# Sheet1.net
KiCad netlist of a schematic drawn in Altium Designer
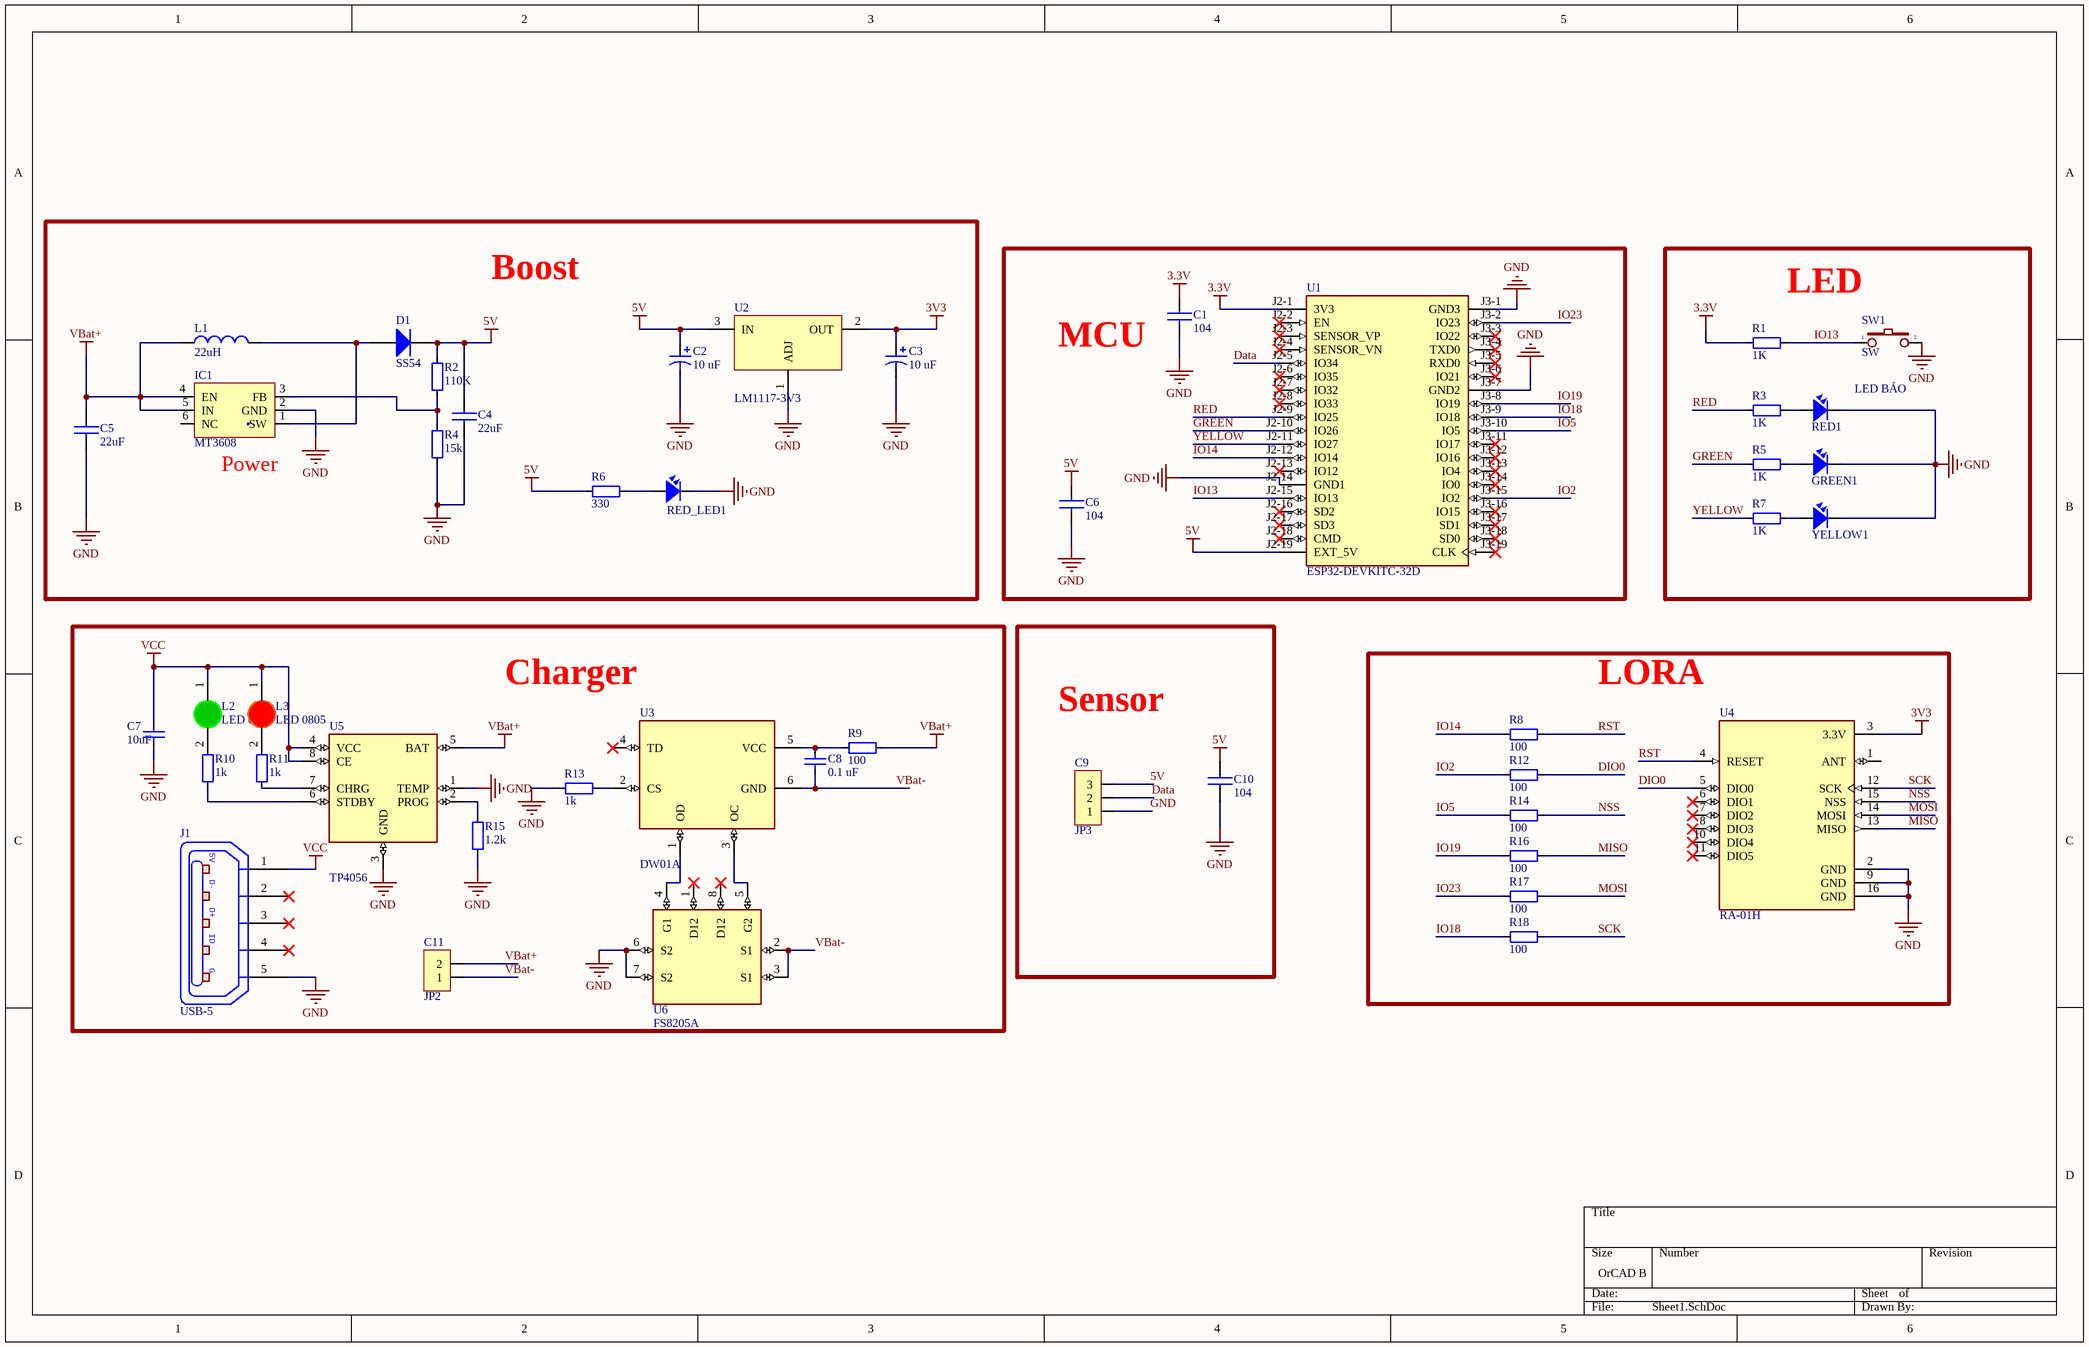
[diagram p0: Sheet1.SchDoc]

(export (version "E")
  (design (tool "Eeschema 10.0.6"))
  (components
    (comp (ref "C1")
      (value "104")
      (footprint "CAP0603")
      (description "CAP CER 30PF 50V NPO 0603")
      (fields
        (field (name "MANUFACTURER") "Yageo")
        (field (name "MANUFACTURER PART NUMBER") "CC0603JRNPO9BN300")
      )
      (libsource (lib "KhanhBK_SCH_Lib_6") (part "CC0603JRNPO9BN300"))
    )
    (comp (ref "C2")
      (value "10 uF")
      (footprint "C3MM")
      (description "Polarized Capacitor (Axial)")
      (fields (field (name "PUBLISHER") "Altium Limited"))
      (libsource (lib "My Library") (part "Cap Pol"))
    )
    (comp (ref "C3")
      (value "10 uF")
      (footprint "C3MM")
      (description "Polarized Capacitor (Axial)")
      (fields (field (name "PUBLISHER") "Altium Limited"))
      (libsource (lib "My Library") (part "Cap Pol"))
    )
    (comp (ref "C4")
      (value "22uF")
      (footprint "CAP0603")
      (description "CAP CER 30PF 50V NPO 0603")
      (fields
        (field (name "MANUFACTURER") "Yageo")
        (field (name "MANUFACTURER PART NUMBER") "CC0603JRNPO9BN300")
      )
      (libsource (lib "KhanhBK_SCH_Lib_6") (part "CC0603JRNPO9BN300"))
    )
    (comp (ref "C5")
      (value "22uF")
      (footprint "CAP0603")
      (description "CAP CER 30PF 50V NPO 0603")
      (fields
        (field (name "MANUFACTURER") "Yageo")
        (field (name "MANUFACTURER PART NUMBER") "CC0603JRNPO9BN300")
      )
      (libsource (lib "KhanhBK_SCH_Lib_6") (part "CC0603JRNPO9BN300"))
    )
    (comp (ref "C6")
      (value "104")
      (footprint "CAP0603")
      (description "CAP CER 30PF 50V NPO 0603")
      (fields
        (field (name "MANUFACTURER") "Yageo")
        (field (name "MANUFACTURER PART NUMBER") "CC0603JRNPO9BN300")
      )
      (libsource (lib "KhanhBK_SCH_Lib_6") (part "CC0603JRNPO9BN300"))
    )
    (comp (ref "C7")
      (value "10uF")
      (footprint "CAP_0805")
      (description "Capacitor")
      (fields (field (name "PUBLISHER") "Altium Limited"))
      (libsource (lib "My Library") (part "CapSMD"))
    )
    (comp (ref "C8")
      (value "0.1 uF")
      (footprint "CAP_0805")
      (description "Capacitor")
      (fields (field (name "PUBLISHER") "Altium Limited"))
      (libsource (lib "My Library") (part "CapSMD"))
    )
    (comp (ref "C9")
      (value "JP3")
      (footprint "JP3-C1T")
      (description "WR-PHD 2.54 mm Angled Socket Header")
      (fields
        (field (name "MANUFACTURER") "Würth Elektronik eiSos GmbH")
        (field (name "PARTNO") "613003143121")
        (field (name "CREATED BY") "Karrer Zheng")
      )
      (libsource (lib "KhanhBK_SCH_Library_1") (part "JP3"))
    )
    (comp (ref "C10")
      (value "104")
      (footprint "CAP0603")
      (description "CAP CER 30PF 50V NPO 0603")
      (fields
        (field (name "MANUFACTURER") "Yageo")
        (field (name "MANUFACTURER PART NUMBER") "CC0603JRNPO9BN300")
      )
      (libsource (lib "KhanhBK_SCH_Lib_6") (part "CC0603JRNPO9BN300"))
    )
    (comp (ref "C11")
      (value "JP2")
      (footprint "JP2-C1T")
      (description "WR-PHD 2.54 mm Angled Socket Header")
      (fields
        (field (name "MANUFACTURER") "Würth Elektronik eiSos GmbH")
        (field (name "PARTNO") "613002143121")
        (field (name "CREATED BY") "Karrer Zheng")
      )
      (libsource (lib "KhanhBK_SCH_Library_1") (part "JP2"))
    )
    (comp (ref "D1")
      (value "SS54")
      (footprint "DIODE/POW/1A")
      (description "Diode Power")
      (fields (field (name "PUBLISHER") "Altium Limited"))
      (libsource (lib "Cty1") (part "Diode Power"))
    )
    (comp (ref "GREEN1")
      (value "LED")
      (footprint "LED-3MM-GREEN")
      (description "LED Single colour Green and Red")
      (libsource (lib "KhanhBK_SCH_Library_1") (part "LED"))
    )
    (comp (ref "IC1") (value "MT3608") (footprint "TSOP 2") (libsource (lib "MT3608") (part "MT3608")))
    (comp (ref "J1")
      (value "USB-5")
      (footprint "USB-M1")
      (fields
        (field (name "MANUFACTURER") "FCI")
        (field (name "MANUFACTURER PART NUMBER") "10118193-0001LF")
        (field (name ".CREATOR") "MM")
        (field (name ".CHECKED PCB") "RF")
        (field (name ".CHECKED SCH") "MM")
      )
      (libsource (lib "My Library") (part "USB-5"))
    )
    (comp (ref "L1")
      (value "22uH")
      (footprint "IND_400_500_212x114_SMD")
      (description "1mH Shielded Wirewound Inductor 600mA 1.82Ohm Max Nonstandard")
      (fields (field (name "MANUFACTURER") "Coilcraft") (field (name "MANUFACTURER PART NUMBER") "74477030"))
      (libsource (lib "Altium_Lib_by_KhueNguyenCreator") (part "IND_1mH-0.6A-20%-SMD"))
    )
    (comp (ref "L2")
      (value "LED 0805")
      (footprint "LED-0805-Green")
      (description "Dán")
      (libsource (lib "Altium_Lib_by_KhueNguyenCreator") (part "LED 0805 Xanh La"))
    )
    (comp (ref "L3")
      (value "LED 0805")
      (footprint "LED-0805-Red")
      (description "Dán")
      (libsource (lib "Altium_Lib_by_KhueNguyenCreator") (part "LED 0805 Do"))
    )
    (comp (ref "R1")
      (value "1K")
      (footprint "RES-SMD-0805")
      (description "Resistor")
      (fields
        (field (name "MANUFACTURER") "Generic Components")
        (field (name "PUBLISHER") "Altium Hobart Technology Centre")
      )
      (libsource (lib "My Library") (part "Resistor - SMD"))
    )
    (comp (ref "R2")
      (value "110K")
      (footprint "RES-SMD-0805")
      (description "Resistor")
      (fields
        (field (name "MANUFACTURER") "Generic Components")
        (field (name "PUBLISHER") "Altium Hobart Technology Centre")
      )
      (libsource (lib "My Library") (part "Resistor - SMD"))
    )
    (comp (ref "R3")
      (value "1K")
      (footprint "RES-SMD-0805")
      (description "Resistor")
      (fields
        (field (name "MANUFACTURER") "Generic Components")
        (field (name "PUBLISHER") "Altium Hobart Technology Centre")
      )
      (libsource (lib "My Library") (part "Resistor - SMD"))
    )
    (comp (ref "R4")
      (value "15k")
      (footprint "RES-SMD-0805")
      (description "Resistor")
      (fields
        (field (name "MANUFACTURER") "Generic Components")
        (field (name "PUBLISHER") "Altium Hobart Technology Centre")
      )
      (libsource (lib "My Library") (part "Resistor - SMD"))
    )
    (comp (ref "R5")
      (value "1K")
      (footprint "RES-SMD-0805")
      (description "Resistor")
      (fields
        (field (name "MANUFACTURER") "Generic Components")
        (field (name "PUBLISHER") "Altium Hobart Technology Centre")
      )
      (libsource (lib "My Library") (part "Resistor - SMD"))
    )
    (comp (ref "R6")
      (value "330")
      (footprint "RES-SMD-0805")
      (description "Resistor")
      (fields
        (field (name "MANUFACTURER") "Generic Components")
        (field (name "PUBLISHER") "Altium Hobart Technology Centre")
      )
      (libsource (lib "My Library") (part "Resistor - SMD"))
    )
    (comp (ref "R7")
      (value "1K")
      (footprint "RES-SMD-0805")
      (description "Resistor")
      (fields
        (field (name "MANUFACTURER") "Generic Components")
        (field (name "PUBLISHER") "Altium Hobart Technology Centre")
      )
      (libsource (lib "My Library") (part "Resistor - SMD"))
    )
    (comp (ref "R8")
      (value "100")
      (footprint "RES-SMD-0805")
      (description "Resistor")
      (fields
        (field (name "MANUFACTURER") "Generic Components")
        (field (name "PUBLISHER") "Altium Hobart Technology Centre")
      )
      (libsource (lib "My Library") (part "Resistor - SMD"))
    )
    (comp (ref "R9")
      (value "100")
      (footprint "RES-SMD-0805")
      (description "Resistor")
      (fields
        (field (name "MANUFACTURER") "Generic Components")
        (field (name "PUBLISHER") "Altium Hobart Technology Centre")
      )
      (libsource (lib "My Library") (part "Resistor - SMD"))
    )
    (comp (ref "R10")
      (value "1k")
      (footprint "RES-SMD-0805")
      (description "Resistor")
      (fields
        (field (name "MANUFACTURER") "Generic Components")
        (field (name "PUBLISHER") "Altium Hobart Technology Centre")
      )
      (libsource (lib "My Library") (part "Resistor - SMD"))
    )
    (comp (ref "R11")
      (value "1k")
      (footprint "RES-SMD-0805")
      (description "Resistor")
      (fields
        (field (name "MANUFACTURER") "Generic Components")
        (field (name "PUBLISHER") "Altium Hobart Technology Centre")
      )
      (libsource (lib "My Library") (part "Resistor - SMD"))
    )
    (comp (ref "R12")
      (value "100")
      (footprint "RES-SMD-0805")
      (description "Resistor")
      (fields
        (field (name "MANUFACTURER") "Generic Components")
        (field (name "PUBLISHER") "Altium Hobart Technology Centre")
      )
      (libsource (lib "My Library") (part "Resistor - SMD"))
    )
    (comp (ref "R13")
      (value "1k")
      (footprint "RES-SMD-0805")
      (description "Resistor")
      (fields
        (field (name "MANUFACTURER") "Generic Components")
        (field (name "PUBLISHER") "Altium Hobart Technology Centre")
      )
      (libsource (lib "My Library") (part "Resistor - SMD"))
    )
    (comp (ref "R14")
      (value "100")
      (footprint "RES-SMD-0805")
      (description "Resistor")
      (fields
        (field (name "MANUFACTURER") "Generic Components")
        (field (name "PUBLISHER") "Altium Hobart Technology Centre")
      )
      (libsource (lib "My Library") (part "Resistor - SMD"))
    )
    (comp (ref "R15")
      (value "1.2k")
      (footprint "RES-SMD-0805")
      (description "Resistor")
      (fields
        (field (name "MANUFACTURER") "Generic Components")
        (field (name "PUBLISHER") "Altium Hobart Technology Centre")
      )
      (libsource (lib "My Library") (part "Resistor - SMD"))
    )
    (comp (ref "R16")
      (value "100")
      (footprint "RES-SMD-0805")
      (description "Resistor")
      (fields
        (field (name "MANUFACTURER") "Generic Components")
        (field (name "PUBLISHER") "Altium Hobart Technology Centre")
      )
      (libsource (lib "My Library") (part "Resistor - SMD"))
    )
    (comp (ref "R17")
      (value "100")
      (footprint "RES-SMD-0805")
      (description "Resistor")
      (fields
        (field (name "MANUFACTURER") "Generic Components")
        (field (name "PUBLISHER") "Altium Hobart Technology Centre")
      )
      (libsource (lib "My Library") (part "Resistor - SMD"))
    )
    (comp (ref "R18")
      (value "100")
      (footprint "RES-SMD-0805")
      (description "Resistor")
      (fields
        (field (name "MANUFACTURER") "Generic Components")
        (field (name "PUBLISHER") "Altium Hobart Technology Centre")
      )
      (libsource (lib "My Library") (part "Resistor - SMD"))
    )
    (comp (ref "RED1")
      (value "LED")
      (footprint "LED-3MM-RED")
      (description "LED Single colour Green and Red")
      (libsource (lib "KhanhBK_SCH_Library_1") (part "LED"))
    )
    (comp (ref "RED_LED1")
      (value "LED")
      (footprint "LED-3MM-RED")
      (description "LED Single colour Green and Red")
      (libsource (lib "KhanhBK_SCH_Library_1") (part "LED"))
    )
    (comp (ref "SW1")
      (value "SW")
      (footprint "SW1-SMD")
      (description "Switch button 2 pin")
      (libsource (lib "KhanhBK_SCH_Library_1") (part "SW2"))
    )
    (comp (ref "U1")
      (value "ESP32-DEVKITC-32D")
      (footprint "MODULE_ESP32-DEVKITC-32D")
      (description "WiFi Development Tools (802.11) ESP32 General Development Kit, ESP32-WROOM-32D on the board")
      (fields (field (name "MF") "Espressif Systems"))
      (libsource (lib "ESP32-DEVKITC-32D") (part "ESP32-DEVKITC-32D"))
    )
    (comp (ref "U2")
      (value "LM1117-3V3")
      (footprint "LM1117-SOP")
      (description "800mA Low-Dropout Linear Regulator")
      (fields (field (name "CREATOR") "Nguyen Ba Bien"))
      (libsource (lib "My Library") (part "LM1117-ADJ"))
    )
    (comp (ref "U3")
      (value "DW01A")
      (footprint "SOT23-6")
      (description "One Cell Lithium-ion/Polymer Battery Protection IC")
      (libsource (lib "My Library") (part "DW01A"))
    )
    (comp (ref "U4")
      (value "RA-01H")
      (footprint "XCVR_RA-01H")
      (fields (field (name "MF") "AI-Thinker"))
      (libsource (lib "RA-01H") (part "RA-01H"))
    )
    (comp (ref "U5")
      (value "TP4056")
      (footprint "TP4056")
      (description "Complete single cell Li-Ion battery with a constant current / constant voltage linear charger")
      (libsource (lib "My Library") (part "TP4056"))
    )
    (comp (ref "U6") (value "FS8205A") (footprint "FS8205A") (libsource (lib "My Library") (part "FS8205A")))
    (comp (ref "YELLOW1")
      (value "LED")
      (footprint "LED-3MM-YELLOW")
      (description "LED Single colour Green and Red")
      (libsource (lib "KhanhBK_SCH_Library_1") (part "LED"))
    )
  )
  (nets
    (net (code "1") (name "/DIO0") (class "Default")
      (node (ref "R12") (pin "2") (pinfunction "2_2") (pintype "passive"))
      (node (ref "U4") (pin "5") (pinfunction "DIO0_5") (pintype "bidirectional"))
    )
    (net (code "2") (name "/Data") (class "Default")
      (node (ref "C9") (pin "2") (pinfunction "2_2") (pintype "passive"))
      (node (ref "U1") (pin "J2-5") (pinfunction "IO34_J2-5") (pintype "bidirectional"))
    )
    (net (code "3") (name "/GREEN") (class "Default")
      (node (ref "R5") (pin "1") (pinfunction "1_1") (pintype "passive"))
      (node (ref "U1") (pin "J2-10") (pinfunction "IO26_J2-10") (pintype "bidirectional"))
    )
    (net (code "4") (name "/IO2") (class "Default")
      (node (ref "R12") (pin "1") (pinfunction "1_1") (pintype "passive"))
      (node (ref "U1") (pin "J3-15") (pinfunction "IO2_J3-15") (pintype "bidirectional"))
    )
    (net (code "5") (name "/IO5") (class "Default")
      (node (ref "R14") (pin "1") (pinfunction "1_1") (pintype "passive"))
      (node (ref "U1") (pin "J3-10") (pinfunction "IO5_J3-10") (pintype "bidirectional"))
    )
    (net (code "6") (name "/IO13") (class "Default")
      (node (ref "R1") (pin "2") (pinfunction "2_2") (pintype "passive"))
      (node (ref "SW1") (pin "1") (pinfunction "1_1") (pintype "passive"))
      (node (ref "U1") (pin "J2-15") (pinfunction "IO13_J2-15") (pintype "bidirectional"))
    )
    (net (code "7") (name "/IO14") (class "Default")
      (node (ref "R8") (pin "1") (pinfunction "1_1") (pintype "passive"))
      (node (ref "U1") (pin "J2-12") (pinfunction "IO14_J2-12") (pintype "bidirectional"))
    )
    (net (code "8") (name "/IO18") (class "Default")
      (node (ref "R18") (pin "1") (pinfunction "1_1") (pintype "passive"))
      (node (ref "U1") (pin "J3-9") (pinfunction "IO18_J3-9") (pintype "bidirectional"))
    )
    (net (code "9") (name "/IO19") (class "Default")
      (node (ref "R16") (pin "1") (pinfunction "1_1") (pintype "passive"))
      (node (ref "U1") (pin "J3-8") (pinfunction "IO19_J3-8") (pintype "bidirectional"))
    )
    (net (code "10") (name "/IO23") (class "Default")
      (node (ref "R17") (pin "1") (pinfunction "1_1") (pintype "passive"))
      (node (ref "U1") (pin "J3-2") (pinfunction "IO23_J3-2") (pintype "bidirectional"))
    )
    (net (code "11") (name "/MISO") (class "Default")
      (node (ref "R16") (pin "2") (pinfunction "2_2") (pintype "passive"))
      (node (ref "U4") (pin "13") (pinfunction "MISO_13") (pintype "output"))
    )
    (net (code "12") (name "/MOSI") (class "Default")
      (node (ref "R17") (pin "2") (pinfunction "2_2") (pintype "passive"))
      (node (ref "U4") (pin "14") (pinfunction "MOSI_14") (pintype "input"))
    )
    (net (code "13") (name "/NSS") (class "Default")
      (node (ref "R14") (pin "2") (pinfunction "2_2") (pintype "passive"))
      (node (ref "U4") (pin "15") (pinfunction "NSS_15") (pintype "input"))
    )
    (net (code "14") (name "/RED") (class "Default")
      (node (ref "R3") (pin "1") (pinfunction "1_1") (pintype "passive"))
      (node (ref "U1") (pin "J2-9") (pinfunction "IO25_J2-9") (pintype "bidirectional"))
    )
    (net (code "15") (name "/RST") (class "Default")
      (node (ref "R8") (pin "2") (pinfunction "2_2") (pintype "passive"))
      (node (ref "U4") (pin "4") (pinfunction "RESET_4") (pintype "input"))
    )
    (net (code "16") (name "/SCK") (class "Default")
      (node (ref "R18") (pin "2") (pinfunction "2_2") (pintype "passive"))
      (node (ref "U4") (pin "12") (pinfunction "SCK_12") (pintype "input"))
    )
    (net (code "17") (name "/VBat-") (class "Default")
      (node (ref "C11") (pin "1") (pinfunction "1_1") (pintype "passive"))
      (node (ref "C8") (pin "1") (pinfunction "1_1") (pintype "passive"))
      (node (ref "U3") (pin "6") (pinfunction "GND_6") (pintype "power_in"))
      (node (ref "U6") (pin "2") (pinfunction "S1_2") (pintype "bidirectional"))
      (node (ref "U6") (pin "3") (pinfunction "S1_3") (pintype "bidirectional"))
    )
    (net (code "18") (name "/YELLOW") (class "Default")
      (node (ref "R7") (pin "1") (pinfunction "1_1") (pintype "passive"))
      (node (ref "U1") (pin "J2-11") (pinfunction "IO27_J2-11") (pintype "bidirectional"))
    )
    (net (code "19") (name "3.3V") (class "Default")
      (node (ref "C1") (pin "1") (pinfunction "1_1") (pintype "passive"))
      (node (ref "R1") (pin "1") (pinfunction "1_1") (pintype "passive"))
      (node (ref "U1") (pin "J2-1") (pinfunction "3V3_J2-1") (pintype "power_in"))
    )
    (net (code "20") (name "3V3") (class "Default")
      (node (ref "C3") (pin "1") (pinfunction "1_1") (pintype "passive"))
      (node (ref "U2") (pin "2") (pinfunction "OUT_2") (pintype "passive"))
      (node (ref "U4") (pin "3") (pinfunction "3.3V_3") (pintype "power_in"))
    )
    (net (code "21") (name "5V") (class "Default")
      (node (ref "C10") (pin "1") (pinfunction "1_1") (pintype "passive"))
      (node (ref "C2") (pin "1") (pinfunction "1_1") (pintype "passive"))
      (node (ref "C4") (pin "1") (pinfunction "1_1") (pintype "passive"))
      (node (ref "C6") (pin "1") (pinfunction "1_1") (pintype "passive"))
      (node (ref "C9") (pin "3") (pinfunction "3_3") (pintype "passive"))
      (node (ref "D1") (pin "2") (pinfunction "K_2") (pintype "passive"))
      (node (ref "R2") (pin "2") (pinfunction "2_2") (pintype "passive"))
      (node (ref "R6") (pin "1") (pinfunction "1_1") (pintype "passive"))
      (node (ref "U1") (pin "J2-19") (pinfunction "EXT_5V_J2-19") (pintype "power_in"))
      (node (ref "U2") (pin "3") (pinfunction "IN_3") (pintype "passive"))
    )
    (net (code "22") (name "GND") (class "Default")
      (node (ref "C1") (pin "2") (pinfunction "2_2") (pintype "passive"))
      (node (ref "C10") (pin "2") (pinfunction "2_2") (pintype "passive"))
      (node (ref "C2") (pin "2") (pinfunction "2_2") (pintype "passive"))
      (node (ref "C3") (pin "2") (pinfunction "2_2") (pintype "passive"))
      (node (ref "C4") (pin "2") (pinfunction "2_2") (pintype "passive"))
      (node (ref "C5") (pin "2") (pinfunction "2_2") (pintype "passive"))
      (node (ref "C6") (pin "2") (pinfunction "2_2") (pintype "passive"))
      (node (ref "C7") (pin "1") (pinfunction "1_1") (pintype "passive"))
      (node (ref "C9") (pin "1") (pinfunction "1_1") (pintype "passive"))
      (node (ref "GREEN1") (pin "2") (pinfunction "2_2") (pintype "passive"))
      (node (ref "IC1") (pin "2") (pinfunction "GND_2") (pintype "power_in"))
      (node (ref "J1") (pin "5") (pinfunction "P5_5") (pintype "passive"))
      (node (ref "R13") (pin "1") (pinfunction "1_1") (pintype "passive"))
      (node (ref "R15") (pin "1") (pinfunction "1_1") (pintype "passive"))
      (node (ref "R4") (pin "1") (pinfunction "1_1") (pintype "passive"))
      (node (ref "RED1") (pin "2") (pinfunction "2_2") (pintype "passive"))
      (node (ref "RED_LED1") (pin "2") (pinfunction "2_2") (pintype "passive"))
      (node (ref "SW1") (pin "2") (pinfunction "2_2") (pintype "passive"))
      (node (ref "U1") (pin "J2-14") (pinfunction "GND1_J2-14") (pintype "power_in"))
      (node (ref "U1") (pin "J3-1") (pinfunction "GND3_J3-1") (pintype "power_in"))
      (node (ref "U1") (pin "J3-7") (pinfunction "GND2_J3-7") (pintype "power_in"))
      (node (ref "U2") (pin "1") (pinfunction "ADJ_1") (pintype "passive"))
      (node (ref "U4") (pin "16") (pinfunction "GND_16") (pintype "power_in"))
      (node (ref "U4") (pin "2") (pinfunction "GND_2") (pintype "power_in"))
      (node (ref "U4") (pin "9") (pinfunction "GND_9") (pintype "power_in"))
      (node (ref "U5") (pin "1") (pinfunction "TEMP_1") (pintype "bidirectional"))
      (node (ref "U5") (pin "3") (pinfunction "GND_3") (pintype "bidirectional"))
      (node (ref "U6") (pin "6") (pinfunction "S2_6") (pintype "bidirectional"))
      (node (ref "U6") (pin "7") (pinfunction "S2_7") (pintype "bidirectional"))
      (node (ref "YELLOW1") (pin "2") (pinfunction "2_2") (pintype "passive"))
    )
    (net (code "23") (name "Net-(D1-A)") (class "Default")
      (node (ref "D1") (pin "1") (pinfunction "A_1") (pintype "passive"))
      (node (ref "IC1") (pin "1") (pinfunction "SW_1") (pintype "power_in"))
      (node (ref "L1") (pin "2") (pinfunction "2_2") (pintype "passive"))
    )
    (net (code "24") (name "Net-(GREEN1-Pad1)") (class "Default")
      (node (ref "GREEN1") (pin "1") (pinfunction "1_1") (pintype "passive"))
      (node (ref "R5") (pin "2") (pinfunction "2_2") (pintype "passive"))
    )
    (net (code "25") (name "Net-(IC1-FB)") (class "Default")
      (node (ref "IC1") (pin "3") (pinfunction "FB_3") (pintype "power_in"))
      (node (ref "R2") (pin "1") (pinfunction "1_1") (pintype "passive"))
      (node (ref "R4") (pin "2") (pinfunction "2_2") (pintype "passive"))
    )
    (net (code "26") (name "Net-(L2-K)") (class "Default")
      (node (ref "L2") (pin "2") (pinfunction "K_2") (pintype "passive"))
      (node (ref "R10") (pin "2") (pinfunction "2_2") (pintype "passive"))
    )
    (net (code "27") (name "Net-(L3-K)") (class "Default")
      (node (ref "L3") (pin "2") (pinfunction "K_2") (pintype "passive"))
      (node (ref "R11") (pin "2") (pinfunction "2_2") (pintype "passive"))
    )
    (net (code "28") (name "Net-(R3-Pad2)") (class "Default")
      (node (ref "R3") (pin "2") (pinfunction "2_2") (pintype "passive"))
      (node (ref "RED1") (pin "1") (pinfunction "1_1") (pintype "passive"))
    )
    (net (code "29") (name "Net-(R6-Pad2)") (class "Default")
      (node (ref "R6") (pin "2") (pinfunction "2_2") (pintype "passive"))
      (node (ref "RED_LED1") (pin "1") (pinfunction "1_1") (pintype "passive"))
    )
    (net (code "30") (name "Net-(R7-Pad2)") (class "Default")
      (node (ref "R7") (pin "2") (pinfunction "2_2") (pintype "passive"))
      (node (ref "YELLOW1") (pin "1") (pinfunction "1_1") (pintype "passive"))
    )
    (net (code "31") (name "Net-(U3-CS)") (class "Default")
      (node (ref "R13") (pin "2") (pinfunction "2_2") (pintype "passive"))
      (node (ref "U3") (pin "2") (pinfunction "CS_2") (pintype "bidirectional"))
    )
    (net (code "32") (name "Net-(U3-OC)") (class "Default")
      (node (ref "U3") (pin "3") (pinfunction "OC_3") (pintype "bidirectional"))
      (node (ref "U6") (pin "5") (pinfunction "G2_5") (pintype "bidirectional"))
    )
    (net (code "33") (name "Net-(U3-OD)") (class "Default")
      (node (ref "U3") (pin "1") (pinfunction "OD_1") (pintype "bidirectional"))
      (node (ref "U6") (pin "4") (pinfunction "G1_4") (pintype "bidirectional"))
    )
    (net (code "34") (name "Net-(U3-VCC)") (class "Default")
      (node (ref "C8") (pin "2") (pinfunction "2_2") (pintype "passive"))
      (node (ref "R9") (pin "1") (pinfunction "1_1") (pintype "passive"))
      (node (ref "U3") (pin "5") (pinfunction "VCC_5") (pintype "power_in"))
    )
    (net (code "35") (name "Net-(U5-CHRG)") (class "Default")
      (node (ref "R11") (pin "1") (pinfunction "1_1") (pintype "passive"))
      (node (ref "U5") (pin "7") (pinfunction "CHRG_7") (pintype "bidirectional"))
    )
    (net (code "36") (name "Net-(U5-PROG)") (class "Default")
      (node (ref "R15") (pin "2") (pinfunction "2_2") (pintype "passive"))
      (node (ref "U5") (pin "2") (pinfunction "PROG_2") (pintype "bidirectional"))
    )
    (net (code "37") (name "Net-(U5-STDBY)") (class "Default")
      (node (ref "R10") (pin "1") (pinfunction "1_1") (pintype "passive"))
      (node (ref "U5") (pin "6") (pinfunction "STDBY_6") (pintype "bidirectional"))
    )
    (net (code "38") (name "VBat+") (class "Default")
      (node (ref "C11") (pin "2") (pinfunction "2_2") (pintype "passive"))
      (node (ref "C5") (pin "1") (pinfunction "1_1") (pintype "passive"))
      (node (ref "IC1") (pin "4") (pinfunction "EN_4") (pintype "power_in"))
      (node (ref "IC1") (pin "5") (pinfunction "IN_5") (pintype "power_in"))
      (node (ref "L1") (pin "1") (pinfunction "1_1") (pintype "passive"))
      (node (ref "R9") (pin "2") (pinfunction "2_2") (pintype "passive"))
      (node (ref "U5") (pin "5") (pinfunction "BAT_5") (pintype "bidirectional"))
    )
    (net (code "39") (name "VCC") (class "Default")
      (node (ref "C7") (pin "2") (pinfunction "2_2") (pintype "passive"))
      (node (ref "J1") (pin "1") (pinfunction "P1_1") (pintype "passive"))
      (node (ref "L2") (pin "1") (pinfunction "A_1") (pintype "passive"))
      (node (ref "L3") (pin "1") (pinfunction "A_1") (pintype "passive"))
      (node (ref "U5") (pin "4") (pinfunction "VCC_4") (pintype "bidirectional"))
      (node (ref "U5") (pin "8") (pinfunction "CE_8") (pintype "bidirectional"))
    )
    (net (code "40") (name "unconnected-(IC1-NC-Pad6)") (class "Default")
      (node (ref "IC1") (pin "6") (pinfunction "NC_6") (pintype "power_in"))
    )
    (net (code "41") (name "unconnected-(J1-P2-Pad2)") (class "Default")
      (node (ref "J1") (pin "2") (pinfunction "P2_2") (pintype "passive+no_connect"))
    )
    (net (code "42") (name "unconnected-(J1-P3-Pad3)") (class "Default")
      (node (ref "J1") (pin "3") (pinfunction "P3_3") (pintype "passive+no_connect"))
    )
    (net (code "43") (name "unconnected-(J1-P4-Pad4)") (class "Default")
      (node (ref "J1") (pin "4") (pinfunction "P4_4") (pintype "passive+no_connect"))
    )
    (net (code "44") (name "unconnected-(U1-CLK-PadJ3-19)") (class "Default")
      (node (ref "U1") (pin "J3-19") (pinfunction "CLK_J3-19") (pintype "input+no_connect"))
    )
    (net (code "45") (name "unconnected-(U1-CMD-PadJ2-18)") (class "Default")
      (node (ref "U1") (pin "J2-18") (pinfunction "CMD_J2-18") (pintype "bidirectional+no_connect"))
    )
    (net (code "46") (name "unconnected-(U1-EN-PadJ2-2)") (class "Default")
      (node (ref "U1") (pin "J2-2") (pinfunction "EN_J2-2") (pintype "input+no_connect"))
    )
    (net (code "47") (name "unconnected-(U1-IO0-PadJ3-14)") (class "Default")
      (node (ref "U1") (pin "J3-14") (pinfunction "IO0_J3-14") (pintype "bidirectional+no_connect"))
    )
    (net (code "48") (name "unconnected-(U1-IO4-PadJ3-13)") (class "Default")
      (node (ref "U1") (pin "J3-13") (pinfunction "IO4_J3-13") (pintype "bidirectional+no_connect"))
    )
    (net (code "49") (name "unconnected-(U1-IO12-PadJ2-13)") (class "Default")
      (node (ref "U1") (pin "J2-13") (pinfunction "IO12_J2-13") (pintype "bidirectional+no_connect"))
    )
    (net (code "50") (name "unconnected-(U1-IO15-PadJ3-16)") (class "Default")
      (node (ref "U1") (pin "J3-16") (pinfunction "IO15_J3-16") (pintype "bidirectional+no_connect"))
    )
    (net (code "51") (name "unconnected-(U1-IO16-PadJ3-12)") (class "Default")
      (node (ref "U1") (pin "J3-12") (pinfunction "IO16_J3-12") (pintype "bidirectional+no_connect"))
    )
    (net (code "52") (name "unconnected-(U1-IO17-PadJ3-11)") (class "Default")
      (node (ref "U1") (pin "J3-11") (pinfunction "IO17_J3-11") (pintype "bidirectional+no_connect"))
    )
    (net (code "53") (name "unconnected-(U1-IO21-PadJ3-6)") (class "Default")
      (node (ref "U1") (pin "J3-6") (pinfunction "IO21_J3-6") (pintype "bidirectional+no_connect"))
    )
    (net (code "54") (name "unconnected-(U1-IO22-PadJ3-3)") (class "Default")
      (node (ref "U1") (pin "J3-3") (pinfunction "IO22_J3-3") (pintype "bidirectional+no_connect"))
    )
    (net (code "55") (name "unconnected-(U1-IO32-PadJ2-7)") (class "Default")
      (node (ref "U1") (pin "J2-7") (pinfunction "IO32_J2-7") (pintype "bidirectional+no_connect"))
    )
    (net (code "56") (name "unconnected-(U1-IO33-PadJ2-8)") (class "Default")
      (node (ref "U1") (pin "J2-8") (pinfunction "IO33_J2-8") (pintype "bidirectional+no_connect"))
    )
    (net (code "57") (name "unconnected-(U1-IO35-PadJ2-6)") (class "Default")
      (node (ref "U1") (pin "J2-6") (pinfunction "IO35_J2-6") (pintype "bidirectional+no_connect"))
    )
    (net (code "58") (name "unconnected-(U1-RXD0-PadJ3-5)") (class "Default")
      (node (ref "U1") (pin "J3-5") (pinfunction "RXD0_J3-5") (pintype "input+no_connect"))
    )
    (net (code "59") (name "unconnected-(U1-SD0-PadJ3-18)") (class "Default")
      (node (ref "U1") (pin "J3-18") (pinfunction "SD0_J3-18") (pintype "bidirectional+no_connect"))
    )
    (net (code "60") (name "unconnected-(U1-SD1-PadJ3-17)") (class "Default")
      (node (ref "U1") (pin "J3-17") (pinfunction "SD1_J3-17") (pintype "bidirectional+no_connect"))
    )
    (net (code "61") (name "unconnected-(U1-SD2-PadJ2-16)") (class "Default")
      (node (ref "U1") (pin "J2-16") (pinfunction "SD2_J2-16") (pintype "bidirectional+no_connect"))
    )
    (net (code "62") (name "unconnected-(U1-SD3-PadJ2-17)") (class "Default")
      (node (ref "U1") (pin "J2-17") (pinfunction "SD3_J2-17") (pintype "bidirectional+no_connect"))
    )
    (net (code "63") (name "unconnected-(U1-SENSOR_VN-PadJ2-4)") (class "Default")
      (node (ref "U1") (pin "J2-4") (pinfunction "SENSOR_VN_J2-4") (pintype "input+no_connect"))
    )
    (net (code "64") (name "unconnected-(U1-SENSOR_VP-PadJ2-3)") (class "Default")
      (node (ref "U1") (pin "J2-3") (pinfunction "SENSOR_VP_J2-3") (pintype "input+no_connect"))
    )
    (net (code "65") (name "unconnected-(U1-TXD0-PadJ3-4)") (class "Default")
      (node (ref "U1") (pin "J3-4") (pinfunction "TXD0_J3-4") (pintype "output+no_connect"))
    )
    (net (code "66") (name "unconnected-(U3-TD-Pad4)") (class "Default")
      (node (ref "U3") (pin "4") (pinfunction "TD_4") (pintype "bidirectional+no_connect"))
    )
    (net (code "67") (name "unconnected-(U4-ANT-Pad1)") (class "Default")
      (node (ref "U4") (pin "1") (pinfunction "ANT_1") (pintype "bidirectional"))
    )
    (net (code "68") (name "unconnected-(U4-DIO1-Pad6)") (class "Default")
      (node (ref "U4") (pin "6") (pinfunction "DIO1_6") (pintype "bidirectional+no_connect"))
    )
    (net (code "69") (name "unconnected-(U4-DIO2-Pad7)") (class "Default")
      (node (ref "U4") (pin "7") (pinfunction "DIO2_7") (pintype "bidirectional+no_connect"))
    )
    (net (code "70") (name "unconnected-(U4-DIO3-Pad8)") (class "Default")
      (node (ref "U4") (pin "8") (pinfunction "DIO3_8") (pintype "bidirectional+no_connect"))
    )
    (net (code "71") (name "unconnected-(U4-DIO4-Pad10)") (class "Default")
      (node (ref "U4") (pin "10") (pinfunction "DIO4_10") (pintype "bidirectional+no_connect"))
    )
    (net (code "72") (name "unconnected-(U4-DIO5-Pad11)") (class "Default")
      (node (ref "U4") (pin "11") (pinfunction "DIO5_11") (pintype "bidirectional+no_connect"))
    )
    (net (code "73") (name "unconnected-(U6-D12-Pad1)") (class "Default")
      (node (ref "U6") (pin "1") (pinfunction "D12_1") (pintype "bidirectional+no_connect"))
    )
    (net (code "74") (name "unconnected-(U6-D12-Pad8)") (class "Default")
      (node (ref "U6") (pin "8") (pinfunction "D12_8") (pintype "bidirectional+no_connect"))
    )
  )
)
